# Supply.net
KiCad netlist of a schematic drawn in Altium Designer
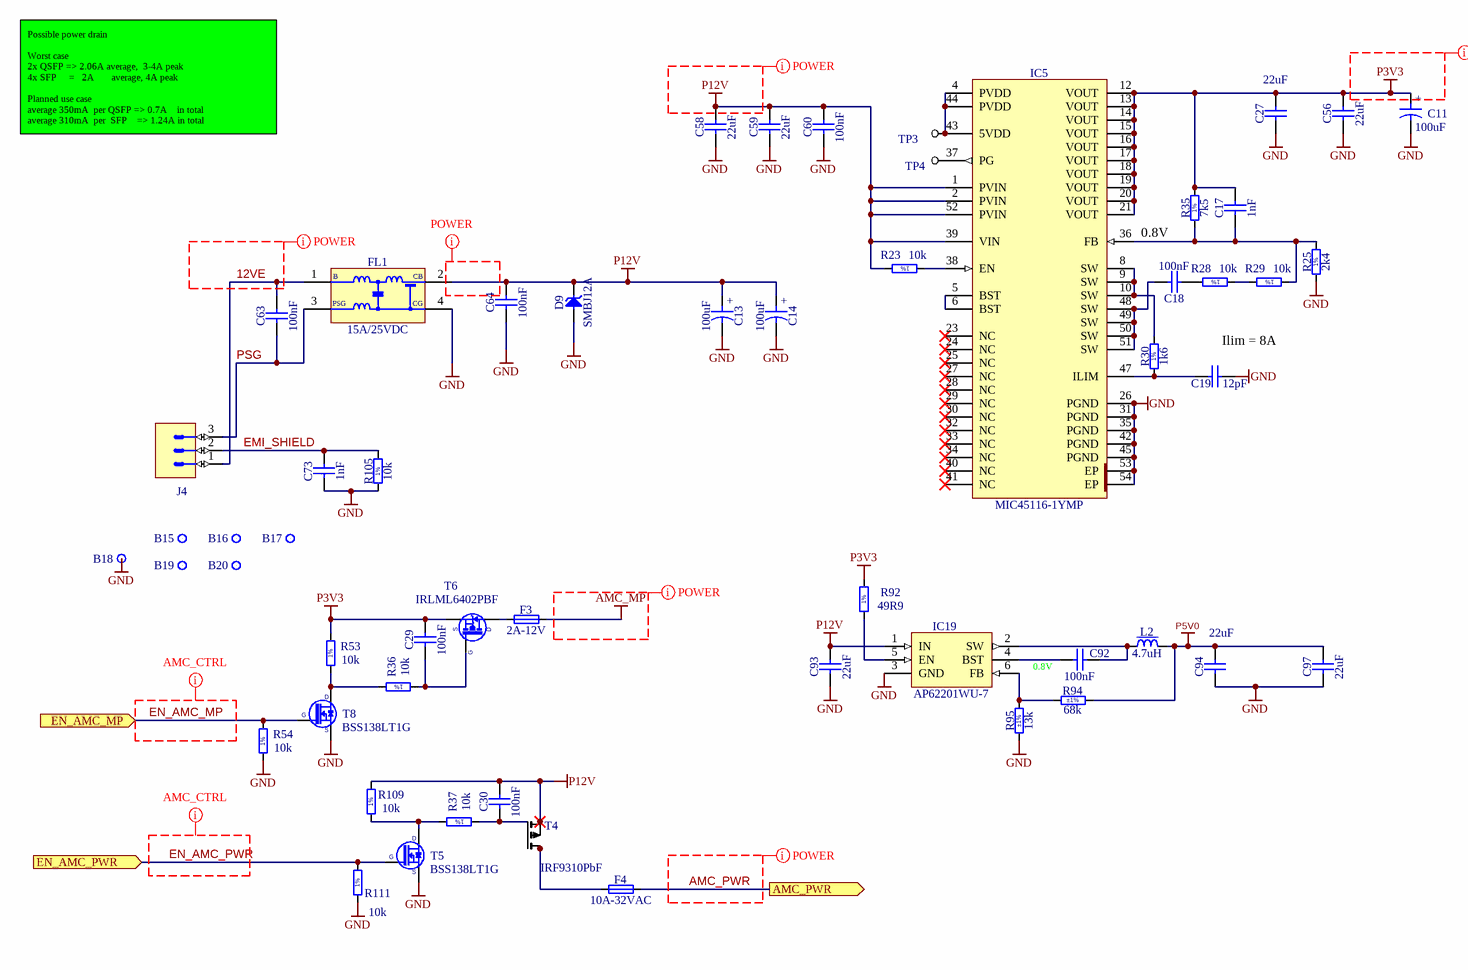
[diagram p0: Supply.SchDoc]

(export (version "E")
  (design (tool "Eeschema 10.0.6"))
  (components
    (comp (ref "B15")
      (value "Plated Hole")
      (footprint "MTG320_550")
      (description "Single Terminal Socket")
      (fields (field (name "PART NUMBER") "PLATED_HOLE3.2_PAD5.5") (field (name "AUTHOR") "CERN DEM JMW"))
      (libsource (lib "Eletro-mechanical") (part "Single Terminal Socket"))
    )
    (comp (ref "B16")
      (value "Plated Hole")
      (footprint "MTG320_550")
      (description "Single Terminal Socket")
      (fields (field (name "PART NUMBER") "PLATED_HOLE3.2_PAD5.5") (field (name "AUTHOR") "CERN DEM JMW"))
      (libsource (lib "Eletro-mechanical") (part "Single Terminal Socket"))
    )
    (comp (ref "B17")
      (value "Plated Hole")
      (footprint "MTG320_550")
      (description "Single Terminal Socket")
      (fields (field (name "PART NUMBER") "PLATED_HOLE3.2_PAD5.5") (field (name "AUTHOR") "CERN DEM JMW"))
      (libsource (lib "Eletro-mechanical") (part "Single Terminal Socket"))
    )
    (comp (ref "B18")
      (value "Plated Hole")
      (footprint "MTG320_550")
      (description "Single Terminal Socket")
      (fields (field (name "PART NUMBER") "PLATED_HOLE3.2_PAD5.5") (field (name "AUTHOR") "CERN DEM JMW"))
      (libsource (lib "Eletro-mechanical") (part "Single Terminal Socket"))
    )
    (comp (ref "B19")
      (value "Plated Hole")
      (footprint "MTG320_550")
      (description "Single Terminal Socket")
      (fields (field (name "PART NUMBER") "PLATED_HOLE3.2_PAD5.5") (field (name "AUTHOR") "CERN DEM JMW"))
      (libsource (lib "Eletro-mechanical") (part "Single Terminal Socket"))
    )
    (comp (ref "B20")
      (value "Plated Hole")
      (footprint "MTG320_550")
      (description "Single Terminal Socket")
      (fields (field (name "PART NUMBER") "PLATED_HOLE3.2_PAD5.5") (field (name "AUTHOR") "CERN DEM JMW"))
      (libsource (lib "Eletro-mechanical") (part "Single Terminal Socket"))
    )
    (comp (ref "C11")
      (value "100uF")
      (footprint "CAPAE660X540N")
      (description "Polarised capacitor")
      (fields
        (field (name "PART NUMBER") "CAE660-540_100UF_16V_20%")
        (field (name "VOLTAGE") "16V")
        (field (name "AUTHOR") "CERN DEM JLC")
      )
      (libsource (lib "Capacitors") (part "Capacitor - polarized"))
    )
    (comp (ref "C13")
      (value "100uF")
      (footprint "CAPAE660X540N")
      (description "Polarised capacitor")
      (fields
        (field (name "PART NUMBER") "CAE660-540_100UF_16V_20%")
        (field (name "VOLTAGE") "16V")
        (field (name "AUTHOR") "CERN DEM JLC")
      )
      (libsource (lib "Capacitors") (part "Capacitor - polarized"))
    )
    (comp (ref "C14")
      (value "100uF")
      (footprint "CAPAE660X540N")
      (description "Polarised capacitor")
      (fields
        (field (name "PART NUMBER") "CAE660-540_100UF_16V_20%")
        (field (name "VOLTAGE") "16V")
        (field (name "AUTHOR") "CERN DEM JLC")
      )
      (libsource (lib "Capacitors") (part "Capacitor - polarized"))
    )
    (comp (ref "C17")
      (value "1nF")
      (footprint "CAPC1005X55N")
      (description "Non-polarised capacitor")
      (fields
        (field (name "PART NUMBER") "CC0402_1NF_50V_10%_X7R")
        (field (name "VOLTAGE") "50V")
        (field (name "AUTHOR") "CERN DEM JLC")
      )
      (libsource (lib "Capacitors") (part "Capacitor - non polarized"))
    )
    (comp (ref "C18")
      (value "100nF")
      (footprint "CAPC1005X55N")
      (description "Non-polarised capacitor")
      (fields
        (field (name "PART NUMBER") "CC0402_100NF_16V_10%_X5R")
        (field (name "VOLTAGE") "16V")
        (field (name "AUTHOR") "CERN DEM JLC")
      )
      (libsource (lib "Capacitors") (part "Capacitor - non polarized"))
    )
    (comp (ref "C19")
      (value "12pF")
      (footprint "CAPC1005X55N")
      (description "Non-polarised capacitor")
      (fields
        (field (name "PART NUMBER") "CC0402_12PF_50V_5%_C0G")
        (field (name "VOLTAGE") "50V")
        (field (name "AUTHOR") "CERN DEM JLC")
      )
      (libsource (lib "Capacitors") (part "Capacitor - non polarized"))
    )
    (comp (ref "C27")
      (value "22uF")
      (footprint "CAPC2012X145N")
      (description "Non-polarised capacitor")
      (fields
        (field (name "PART NUMBER") "CC0805_22UF_25V_20%_X5R")
        (field (name "VOLTAGE") "25V")
        (field (name "AUTHOR") "CERN DEM WB")
      )
      (libsource (lib "Capacitors") (part "Capacitor - non polarized"))
    )
    (comp (ref "C29")
      (value "100nF")
      (footprint "CAPC1005X55N")
      (description "Non-polarised capacitor")
      (fields
        (field (name "PART NUMBER") "CC0402_100NF_16V_10%_X5R")
        (field (name "VOLTAGE") "16V")
        (field (name "AUTHOR") "CERN DEM JLC")
      )
      (libsource (lib "Capacitors") (part "Capacitor - non polarized"))
    )
    (comp (ref "C30")
      (value "100nF")
      (footprint "CAPC1005X55N")
      (description "Non-polarised capacitor")
      (fields
        (field (name "PART NUMBER") "CC0402_100NF_16V_10%_X5R")
        (field (name "VOLTAGE") "16V")
        (field (name "AUTHOR") "CERN DEM JLC")
      )
      (libsource (lib "Capacitors") (part "Capacitor - non polarized"))
    )
    (comp (ref "C56")
      (value "22uF")
      (footprint "CAPC2012X145N")
      (description "Non-polarised capacitor")
      (fields
        (field (name "PART NUMBER") "CC0805_22UF_25V_20%_X5R")
        (field (name "VOLTAGE") "25V")
        (field (name "AUTHOR") "CERN DEM WB")
      )
      (libsource (lib "Capacitors") (part "Capacitor - non polarized"))
    )
    (comp (ref "C58")
      (value "22uF")
      (footprint "CAPC2012X145N")
      (description "Non-polarised capacitor")
      (fields
        (field (name "PART NUMBER") "CC0805_22UF_25V_20%_X5R")
        (field (name "VOLTAGE") "25V")
        (field (name "AUTHOR") "CERN DEM WB")
      )
      (libsource (lib "Capacitors") (part "Capacitor - non polarized"))
    )
    (comp (ref "C59")
      (value "22uF")
      (footprint "CAPC2012X145N")
      (description "Non-polarised capacitor")
      (fields
        (field (name "PART NUMBER") "CC0805_22UF_25V_20%_X5R")
        (field (name "VOLTAGE") "25V")
        (field (name "AUTHOR") "CERN DEM WB")
      )
      (libsource (lib "Capacitors") (part "Capacitor - non polarized"))
    )
    (comp (ref "C60")
      (value "100nF")
      (footprint "CAPC1005X55N")
      (description "Non-polarised capacitor")
      (fields
        (field (name "PART NUMBER") "CC0402_100NF_16V_10%_X5R")
        (field (name "VOLTAGE") "16V")
        (field (name "AUTHOR") "CERN DEM JLC")
      )
      (libsource (lib "Capacitors") (part "Capacitor - non polarized"))
    )
    (comp (ref "C63")
      (value "100nF")
      (footprint "CAPC1005X55N")
      (description "Non-polarised capacitor")
      (fields
        (field (name "PART NUMBER") "CC0402_100NF_16V_10%_X5R")
        (field (name "VOLTAGE") "16V")
        (field (name "AUTHOR") "CERN DEM JLC")
      )
      (libsource (lib "Capacitors") (part "Capacitor - non polarized"))
    )
    (comp (ref "C64")
      (value "100nF")
      (footprint "CAPC1005X55N")
      (description "Non-polarised capacitor")
      (fields
        (field (name "PART NUMBER") "CC0402_100NF_16V_10%_X5R")
        (field (name "VOLTAGE") "16V")
        (field (name "AUTHOR") "CERN DEM JLC")
      )
      (libsource (lib "Capacitors") (part "Capacitor - non polarized"))
    )
    (comp (ref "C73")
      (value "1nF")
      (footprint "CAPC1005X55N")
      (description "Non-polarised capacitor")
      (fields
        (field (name "PART NUMBER") "CC0402_1NF_50V_10%_X7R")
        (field (name "VOLTAGE") "50V")
        (field (name "AUTHOR") "CERN DEM JLC")
      )
      (libsource (lib "Capacitors") (part "Capacitor - non polarized"))
    )
    (comp (ref "C92")
      (value "100nF")
      (footprint "CAPC1005X55N")
      (description "Non-polarised capacitor")
      (fields
        (field (name "PART NUMBER") "CC0402_100NF_16V_10%_X5R")
        (field (name "VOLTAGE") "16V")
        (field (name "AUTHOR") "CERN DEM JLC")
      )
      (libsource (lib "Capacitors") (part "Capacitor - non polarized"))
    )
    (comp (ref "C93")
      (value "22uF")
      (footprint "CAPC2012X145N")
      (description "Non-polarised capacitor")
      (fields
        (field (name "PART NUMBER") "CC0805_22UF_25V_20%_X5R")
        (field (name "VOLTAGE") "25V")
        (field (name "AUTHOR") "CERN DEM WB")
      )
      (libsource (lib "Capacitors") (part "Capacitor - non polarized"))
    )
    (comp (ref "C94")
      (value "22uF")
      (footprint "CAPC2012X145N")
      (description "Non-polarised capacitor")
      (fields
        (field (name "PART NUMBER") "CC0805_22UF_25V_20%_X5R")
        (field (name "VOLTAGE") "25V")
        (field (name "AUTHOR") "CERN DEM WB")
      )
      (libsource (lib "Capacitors") (part "Capacitor - non polarized"))
    )
    (comp (ref "C97")
      (value "22uF")
      (footprint "CAPC2012X145N")
      (description "Non-polarised capacitor")
      (fields
        (field (name "PART NUMBER") "CC0805_22UF_25V_20%_X5R")
        (field (name "VOLTAGE") "25V")
        (field (name "AUTHOR") "CERN DEM WB")
      )
      (libsource (lib "Capacitors") (part "Capacitor - non polarized"))
    )
    (comp (ref "D9")
      (value "SMBJ12A")
      (footprint "DIOM5336X265N")
      (description "Zener Diode")
      (fields
        (field (name "VOLTAGE") "12V")
        (field (name "POWER") "600W")
        (field (name "AUTHOR") "CERN DEM JLC")
      )
      (libsource (lib "ICs And Semiconductors") (part "Diode Zener"))
    )
    (comp (ref "F3")
      (value "2A-12V")
      (footprint "FUSR_LITTELFUSE_1812L200")
      (description "Fuse")
      (fields
        (field (name "PART NUMBER") "FUSR1812_LITTELFUSE_1812L200/12")
        (field (name "MANUFACTURER") "LITTELFUSE")
        (field (name "AUTHOR") "CERN DEM BC")
      )
      (libsource (lib "Eletro-mechanical") (part "Fuse"))
    )
    (comp (ref "F4")
      (value "10A-32VAC")
      (footprint "FUSE_SCHURTER_UST1206")
      (description "Fuse")
      (fields
        (field (name "PART NUMBER") "FUSE_SCHURTER_3413.0328.22")
        (field (name "MANUFACTURER") "SCHURTER")
        (field (name "AUTHOR") "CERN DEM BC")
      )
      (libsource (lib "Eletro-mechanical") (part "Fuse"))
    )
    (comp (ref "FL1")
      (value "15A/25VDC")
      (footprint "FIL_MURATA_BNX016")
      (description "Block Type EMIFIL (LC Combined) SMD Type, BNX01* Serie")
      (fields
        (field (name "PART NUMBER") "FIL_MURATA_BNX016-01")
        (field (name "MANUFACTURER") "MURATA")
        (field (name "AUTHOR") "CERN DEM JLC")
      )
      (libsource (lib "Inductors & Transformers") (part "FIL_MURATA_BNX016"))
    )
    (comp (ref "IC5")
      (value "MIC45116-1YMP")
      (footprint "MICROCHIP_H3QFN88-52LD-PL-3")
      (description "0.8V to 85% PVIN (4.75-19V), 6A Synchronous Step-Down Regulator Module")
      (fields (field (name "MANUFACTURER") "MICROCHIP TECHNOLOGY") (field (name "AUTHOR") "CERN DEM JMW"))
      (libsource (lib "ICs And Semiconductors") (part "MIC45116"))
    )
    (comp (ref "IC19")
      (value "AP62201WU-7")
      (footprint "SOT95P285X110-6N")
      (description "LIGHT LOAD IMPROVED 1.5A SYNCH DC/DC BUCK CONVERTER")
      (fields (field (name "MANUFACTURER") "DIODES INCORPORATED") (field (name "AUTHOR") "GK"))
      (libsource (lib "Regulators_SMPS") (part "PM_AP65111A"))
    )
    (comp (ref "J4")
      (value "~")
      (footprint "PHOENIX_1755749")
      (description "Connector 3 Male")
      (fields
        (field (name "PART NUMBER") "PHOENIX_1755749")
        (field (name "MANUFACTURER") "PHOENIX CONTACT")
        (field (name "AUTHOR") "CERN DEM JLC")
      )
      (libsource (lib "Connectors") (part "Connector 3 Male"))
    )
    (comp (ref "L2")
      (value "4.7uH")
      (footprint "INDM5552X200N")
      (description "Inductor With Core")
      (fields
        (field (name "PART NUMBER") "IND2020_4.7UH_20%_VISHAY_IHLP-2020BZ-11")
        (field (name "POWER") "3.2A")
        (field (name "AUTHOR") "CERN DEM JLC")
      )
      (libsource (lib "Inductors & Transformers") (part "Inductor With Magnetic core"))
    )
    (comp (ref "R23")
      (value "10k")
      (footprint "RESC1005X40N")
      (description "Resistor - 1%")
      (fields
        (field (name "PART NUMBER") "R0402_10K_1%_0.0625W_100PPM")
        (field (name "POWER") "0.0625W")
        (field (name "AUTHOR") "CERN DEM JLC")
      )
      (libsource (lib "Resistors") (part "Resistor - 1%"))
    )
    (comp (ref "R25")
      (value "2k4")
      (footprint "RESC1005X40N")
      (description "Resistor - 1%")
      (fields
        (field (name "PART NUMBER") "R0402_2K4_1%_0.0625W_100PPM")
        (field (name "POWER") "0.0625W")
        (field (name "AUTHOR") "CERN DEM JLC")
      )
      (libsource (lib "Resistors") (part "Resistor - 1%"))
    )
    (comp (ref "R28")
      (value "10k")
      (footprint "RESC1005X40N")
      (description "Resistor - 1%")
      (fields
        (field (name "PART NUMBER") "R0402_10K_1%_0.0625W_100PPM")
        (field (name "POWER") "0.0625W")
        (field (name "AUTHOR") "CERN DEM JLC")
      )
      (libsource (lib "Resistors") (part "Resistor - 1%"))
    )
    (comp (ref "R29")
      (value "10k")
      (footprint "RESC1005X40N")
      (description "Resistor - 1%")
      (fields
        (field (name "PART NUMBER") "R0402_10K_1%_0.0625W_100PPM")
        (field (name "POWER") "0.0625W")
        (field (name "AUTHOR") "CERN DEM JLC")
      )
      (libsource (lib "Resistors") (part "Resistor - 1%"))
    )
    (comp (ref "R30")
      (value "1k6")
      (footprint "RESC1005X40N")
      (description "Resistor - 1%")
      (fields
        (field (name "PART NUMBER") "R0402_1K6_1%_0.0625W_100PPM")
        (field (name "POWER") "0.0625W")
        (field (name "AUTHOR") "CERN DEM JLC")
      )
      (libsource (lib "Resistors") (part "Resistor - 1%"))
    )
    (comp (ref "R35")
      (value "7k5")
      (footprint "RESC1005X40N")
      (description "Resistor - 1%")
      (fields
        (field (name "PART NUMBER") "R0402_7K5_1%_0.0625W_100PPM")
        (field (name "POWER") "0.0625W")
        (field (name "AUTHOR") "CERN DEM JLC")
      )
      (libsource (lib "Resistors") (part "Resistor - 1%"))
    )
    (comp (ref "R36")
      (value "10k")
      (footprint "RESC1005X40N")
      (description "Resistor - 1%")
      (fields
        (field (name "PART NUMBER") "R0402_10K_1%_0.0625W_100PPM")
        (field (name "POWER") "0.0625W")
        (field (name "AUTHOR") "CERN DEM JLC")
      )
      (libsource (lib "Resistors") (part "Resistor - 1%"))
    )
    (comp (ref "R37")
      (value "10k")
      (footprint "RESC1005X40N")
      (description "Resistor - 1%")
      (fields
        (field (name "PART NUMBER") "R0402_10K_1%_0.0625W_100PPM")
        (field (name "POWER") "0.0625W")
        (field (name "AUTHOR") "CERN DEM JLC")
      )
      (libsource (lib "Resistors") (part "Resistor - 1%"))
    )
    (comp (ref "R53")
      (value "10k")
      (footprint "RESC1005X40N")
      (description "Resistor - 1%")
      (fields
        (field (name "PART NUMBER") "R0402_10K_1%_0.0625W_100PPM")
        (field (name "POWER") "0.0625W")
        (field (name "AUTHOR") "CERN DEM JLC")
      )
      (libsource (lib "Resistors") (part "Resistor - 1%"))
    )
    (comp (ref "R54")
      (value "10k")
      (footprint "RESC1005X40N")
      (description "Resistor - 1%")
      (fields
        (field (name "PART NUMBER") "R0402_10K_1%_0.0625W_100PPM")
        (field (name "POWER") "0.0625W")
        (field (name "AUTHOR") "CERN DEM JLC")
      )
      (libsource (lib "Resistors") (part "Resistor - 1%"))
    )
    (comp (ref "R92")
      (value "49R9")
      (footprint "RESC1005X40N")
      (description "Resistor - 1%")
      (fields
        (field (name "PART NUMBER") "R0402_49R9_1%_0.0625W_100PPM")
        (field (name "POWER") "0.0625W")
        (field (name "AUTHOR") "CERN DEM JLC")
      )
      (libsource (lib "Resistors") (part "Resistor - 1%"))
    )
    (comp (ref "R94")
      (value "68k")
      (footprint "RESC1005X40N")
      (description "Resistor - 1%")
      (fields
        (field (name "TOLERANCE") "±1%")
        (field (name "PART NUMBER") "R0402_68K_1%_0.0625W_100PPM")
        (field (name "POWER") "0.0625W")
        (field (name "AUTHOR") "CERN DEM JLC")
      )
      (libsource (lib "Resistors") (part "Resistor - 1%"))
    )
    (comp (ref "R95")
      (value "13k")
      (footprint "RESC1005X40N")
      (description "Resistor - 1%")
      (fields
        (field (name "TOLERANCE") "±1%")
        (field (name "PART NUMBER") "R0402_13K_1%_0.0625W_100PPM")
        (field (name "POWER") "0.0625W")
        (field (name "AUTHOR") "CERN DEM JLC")
      )
      (libsource (lib "Resistors") (part "Resistor - 1%"))
    )
    (comp (ref "R105")
      (value "10k")
      (footprint "RESC1005X40N")
      (description "Resistor - 1%")
      (fields
        (field (name "PART NUMBER") "R0402_10K_1%_0.0625W_100PPM")
        (field (name "POWER") "0.0625W")
        (field (name "AUTHOR") "CERN DEM JLC")
      )
      (libsource (lib "Resistors") (part "Resistor - 1%"))
    )
    (comp (ref "R109")
      (value "10k")
      (footprint "RESC1005X40N")
      (description "Resistor - 1%")
      (fields
        (field (name "PART NUMBER") "R0402_10K_1%_0.0625W_100PPM")
        (field (name "POWER") "0.0625W")
        (field (name "AUTHOR") "CERN DEM JLC")
      )
      (libsource (lib "Resistors") (part "Resistor - 1%"))
    )
    (comp (ref "R111")
      (value "10k")
      (footprint "RESC1005X40N")
      (description "Resistor - 1%")
      (fields
        (field (name "PART NUMBER") "R0402_10K_1%_0.0625W_100PPM")
        (field (name "POWER") "0.0625W")
        (field (name "AUTHOR") "CERN DEM JLC")
      )
      (libsource (lib "Resistors") (part "Resistor - 1%"))
    )
    (comp (ref "T4")
      (value "IRF9310PbF")
      (footprint "so-8")
      (description "PMOS 30V, 4.6mR, 20A, 2.5W")
      (libsource (lib "LIBRARY_SCH") (part "Q_IRF9310"))
    )
    (comp (ref "T5")
      (value "BSS138LT1G")
      (footprint "SOT95P240X110-3N")
      (description "N-CHANNEL MOSFET WITH DIODE")
      (fields (field (name "MANUFACTURER") "ON SEMICONDUCTOR") (field (name "AUTHOR") "CERN DEM JLC"))
      (libsource (lib "ICs And Semiconductors") (part "N-MOSFET-D 1G 2S 3D"))
    )
    (comp (ref "T6")
      (value "IRLML6402PBF")
      (footprint "SOT95P237X112-3N")
      (description "P-CHANNEL MOSFET WITH ZENER DIODE")
      (fields (field (name "MANUFACTURER") "INTERNATIONAL RECTIFIER") (field (name "AUTHOR") "CERN DEM JLC"))
      (libsource (lib "ICs And Semiconductors") (part "P-MOSFET-DZ 1G 2S 3D"))
    )
    (comp (ref "T8")
      (value "BSS138LT1G")
      (footprint "SOT95P240X110-3N")
      (description "N-CHANNEL MOSFET WITH DIODE")
      (fields (field (name "MANUFACTURER") "ON SEMICONDUCTOR") (field (name "AUTHOR") "CERN DEM JLC"))
      (libsource (lib "ICs And Semiconductors") (part "N-MOSFET-D 1G 2S 3D"))
    )
    (comp (ref "TP3")
      (value "TP")
      (footprint "TP")
      (description "Testpoint")
      (libsource (lib "LIBRARY_SCH") (part "TP"))
    )
    (comp (ref "TP4")
      (value "TP")
      (footprint "TP")
      (description "Testpoint")
      (libsource (lib "LIBRARY_SCH") (part "TP"))
    )
  )
  (nets
    (net (code "1") (name "/12VE") (class "Default")
      (node (ref "C63") (pin "2") (pinfunction "2_2") (pintype "passive"))
      (node (ref "FL1") (pin "1") (pinfunction "B_1") (pintype "passive"))
      (node (ref "J4") (pin "1") (pinfunction "1_1") (pintype "bidirectional"))
    )
    (net (code "2") (name "/AMC_PWR") (class "Default")
      (node (ref "F4") (pin "2") (pinfunction "2_2") (pintype "passive"))
    )
    (net (code "3") (name "/EMI_SHIELD") (class "Default")
      (node (ref "C73") (pin "2") (pinfunction "2_2") (pintype "passive"))
      (node (ref "J4") (pin "2") (pinfunction "2_2") (pintype "bidirectional"))
      (node (ref "R105") (pin "2") (pinfunction "2_2") (pintype "passive"))
    )
    (net (code "4") (name "/EN_AMC_MP") (class "Default")
      (node (ref "R54") (pin "2") (pinfunction "2_2") (pintype "passive"))
      (node (ref "T8") (pin "1") (pinfunction "G_1") (pintype "passive"))
    )
    (net (code "5") (name "/EN_AMC_PWR") (class "Default")
      (node (ref "R111") (pin "2") (pinfunction "2_2") (pintype "passive"))
      (node (ref "T5") (pin "1") (pinfunction "G_1") (pintype "passive"))
    )
    (net (code "6") (name "/PSG") (class "Default")
      (node (ref "C63") (pin "1") (pinfunction "1_1") (pintype "passive"))
      (node (ref "FL1") (pin "3") (pinfunction "PSG_3") (pintype "passive"))
      (node (ref "J4") (pin "3") (pinfunction "3_3") (pintype "bidirectional"))
    )
    (net (code "7") (name "AMC_MP") (class "Default")
      (node (ref "F3") (pin "2") (pinfunction "2_2") (pintype "passive"))
    )
    (net (code "8") (name "GND") (class "Default")
      (node (ref "B18") (pin "1") (pinfunction "1_1") (pintype "bidirectional"))
      (node (ref "C11") (pin "2") (pinfunction "2_2") (pintype "passive"))
      (node (ref "C13") (pin "2") (pinfunction "2_2") (pintype "passive"))
      (node (ref "C14") (pin "2") (pinfunction "2_2") (pintype "passive"))
      (node (ref "C19") (pin "1") (pinfunction "1_1") (pintype "passive"))
      (node (ref "C27") (pin "1") (pinfunction "1_1") (pintype "passive"))
      (node (ref "C56") (pin "1") (pinfunction "1_1") (pintype "passive"))
      (node (ref "C58") (pin "1") (pinfunction "1_1") (pintype "passive"))
      (node (ref "C59") (pin "1") (pinfunction "1_1") (pintype "passive"))
      (node (ref "C60") (pin "1") (pinfunction "1_1") (pintype "passive"))
      (node (ref "C64") (pin "1") (pinfunction "1_1") (pintype "passive"))
      (node (ref "C73") (pin "1") (pinfunction "1_1") (pintype "passive"))
      (node (ref "C93") (pin "1") (pinfunction "1_1") (pintype "passive"))
      (node (ref "C94") (pin "1") (pinfunction "1_1") (pintype "passive"))
      (node (ref "C97") (pin "1") (pinfunction "1_1") (pintype "passive"))
      (node (ref "D9") (pin "2") (pinfunction "A_2") (pintype "passive"))
      (node (ref "FL1") (pin "4") (pinfunction "CG_4") (pintype "passive"))
      (node (ref "IC19") (pin "3") (pinfunction "GND_3") (pintype "power_in"))
      (node (ref "IC5") (pin "26") (pinfunction "PGND_26") (pintype "power_in"))
      (node (ref "IC5") (pin "31") (pinfunction "PGND_31") (pintype "power_in"))
      (node (ref "IC5") (pin "35") (pinfunction "PGND_35") (pintype "power_in"))
      (node (ref "IC5") (pin "42") (pinfunction "PGND_42") (pintype "power_in"))
      (node (ref "IC5") (pin "45") (pinfunction "PGND_45") (pintype "power_in"))
      (node (ref "IC5") (pin "53") (pinfunction "EP_53") (pintype "power_in"))
      (node (ref "IC5") (pin "54") (pinfunction "EP_54") (pintype "power_in"))
      (node (ref "R105") (pin "1") (pinfunction "1_1") (pintype "passive"))
      (node (ref "R111") (pin "1") (pinfunction "1_1") (pintype "passive"))
      (node (ref "R25") (pin "1") (pinfunction "1_1") (pintype "passive"))
      (node (ref "R54") (pin "1") (pinfunction "1_1") (pintype "passive"))
      (node (ref "R95") (pin "1") (pinfunction "1_1") (pintype "passive"))
      (node (ref "T5") (pin "2") (pinfunction "S_2") (pintype "passive"))
      (node (ref "T8") (pin "2") (pinfunction "S_2") (pintype "passive"))
    )
    (net (code "9") (name "Net-(C18-Pad1)") (class "Default")
      (node (ref "C18") (pin "1") (pinfunction "1_1") (pintype "passive"))
      (node (ref "R28") (pin "2") (pinfunction "2_2") (pintype "passive"))
    )
    (net (code "10") (name "Net-(C18-Pad2)") (class "Default")
      (node (ref "C18") (pin "2") (pinfunction "2_2") (pintype "passive"))
      (node (ref "IC5") (pin "48") (pinfunction "SW_48") (pintype "passive"))
      (node (ref "IC5") (pin "49") (pinfunction "SW_49") (pintype "passive"))
      (node (ref "IC5") (pin "50") (pinfunction "SW_50") (pintype "passive"))
      (node (ref "IC5") (pin "51") (pinfunction "SW_51") (pintype "passive"))
    )
    (net (code "11") (name "Net-(F4-Pad1)") (class "Default")
      (node (ref "F4") (pin "1") (pinfunction "1_1") (pintype "passive"))
      (node (ref "T4") (pin "5") (pinfunction "D1_5") (pintype "open_collector"))
      (node (ref "T4") (pin "6") (pinfunction "D1_6") (pintype "open_collector"))
      (node (ref "T4") (pin "7") (pinfunction "D1_7") (pintype "open_collector"))
      (node (ref "T4") (pin "8") (pinfunction "D1_8") (pintype "open_collector"))
    )
    (net (code "12") (name "Net-(IC5-5VDD)") (class "Default")
      (node (ref "IC5") (pin "4") (pinfunction "PVDD_4") (pintype "power_in"))
      (node (ref "IC5") (pin "43") (pinfunction "5VDD_43") (pintype "power_in"))
      (node (ref "IC5") (pin "44") (pinfunction "PVDD_44") (pintype "power_in"))
      (node (ref "TP3") (pin "1") (pintype "passive"))
    )
    (net (code "13") (name "Net-(IC5-BST-Pad5)") (class "Default")
      (node (ref "IC5") (pin "5") (pinfunction "BST_5") (pintype "passive"))
      (node (ref "IC5") (pin "6") (pinfunction "BST_6") (pintype "passive"))
    )
    (net (code "14") (name "Net-(IC5-EN)") (class "Default")
      (node (ref "IC5") (pin "38") (pinfunction "EN_38") (pintype "input"))
      (node (ref "R23") (pin "1") (pinfunction "1_1") (pintype "passive"))
    )
    (net (code "15") (name "Net-(IC5-FB)") (class "Default")
      (node (ref "C17") (pin "1") (pinfunction "1_1") (pintype "passive"))
      (node (ref "IC5") (pin "36") (pinfunction "FB_36") (pintype "input"))
      (node (ref "R25") (pin "2") (pinfunction "2_2") (pintype "passive"))
      (node (ref "R29") (pin "1") (pinfunction "1_1") (pintype "passive"))
      (node (ref "R35") (pin "1") (pinfunction "1_1") (pintype "passive"))
    )
    (net (code "16") (name "Net-(IC5-ILIM)") (class "Default")
      (node (ref "C19") (pin "2") (pinfunction "2_2") (pintype "passive"))
      (node (ref "IC5") (pin "47") (pinfunction "ILIM_47") (pintype "passive"))
      (node (ref "R30") (pin "1") (pinfunction "1_1") (pintype "passive"))
    )
    (net (code "17") (name "Net-(IC5-PG)") (class "Default")
      (node (ref "IC5") (pin "37") (pinfunction "PG_37") (pintype "output"))
      (node (ref "TP4") (pin "1") (pintype "passive"))
    )
    (net (code "18") (name "Net-(IC5-SW-Pad10)") (class "Default")
      (node (ref "IC5") (pin "10") (pinfunction "SW_10") (pintype "passive"))
      (node (ref "IC5") (pin "8") (pinfunction "SW_8") (pintype "passive"))
      (node (ref "IC5") (pin "9") (pinfunction "SW_9") (pintype "passive"))
      (node (ref "R30") (pin "2") (pinfunction "2_2") (pintype "passive"))
    )
    (net (code "19") (name "Net-(IC19-BST)") (class "Default")
      (node (ref "C92") (pin "1") (pinfunction "1_1") (pintype "passive"))
      (node (ref "IC19") (pin "4") (pinfunction "BST_4") (pintype "passive"))
    )
    (net (code "20") (name "Net-(IC19-EN)") (class "Default")
      (node (ref "IC19") (pin "5") (pinfunction "EN_5") (pintype "input"))
      (node (ref "R92") (pin "1") (pinfunction "1_1") (pintype "passive"))
    )
    (net (code "21") (name "Net-(IC19-FB)") (class "Default")
      (node (ref "IC19") (pin "6") (pinfunction "FB_6") (pintype "input"))
      (node (ref "R94") (pin "1") (pinfunction "1_1") (pintype "passive"))
      (node (ref "R95") (pin "2") (pinfunction "2_2") (pintype "passive"))
    )
    (net (code "22") (name "Net-(IC19-SW)") (class "Default")
      (node (ref "C92") (pin "2") (pinfunction "2_2") (pintype "passive"))
      (node (ref "IC19") (pin "2") (pinfunction "SW_2") (pintype "output"))
      (node (ref "L2") (pin "1") (pinfunction "1_1") (pintype "passive"))
    )
    (net (code "23") (name "Net-(R28-Pad1)") (class "Default")
      (node (ref "R28") (pin "1") (pinfunction "1_1") (pintype "passive"))
      (node (ref "R29") (pin "2") (pinfunction "2_2") (pintype "passive"))
    )
    (net (code "24") (name "Net-(T4-G1)") (class "Default")
      (node (ref "C30") (pin "1") (pinfunction "1_1") (pintype "passive"))
      (node (ref "R37") (pin "1") (pinfunction "1_1") (pintype "passive"))
      (node (ref "T4") (pin "4") (pinfunction "G1_4") (pintype "input"))
    )
    (net (code "25") (name "Net-(T5-D)") (class "Default")
      (node (ref "R109") (pin "1") (pinfunction "1_1") (pintype "passive"))
      (node (ref "R37") (pin "2") (pinfunction "2_2") (pintype "passive"))
      (node (ref "T5") (pin "3") (pinfunction "D_3") (pintype "passive"))
    )
    (net (code "26") (name "Net-(T6-D)") (class "Default")
      (node (ref "F3") (pin "1") (pinfunction "1_1") (pintype "passive"))
      (node (ref "T6") (pin "3") (pinfunction "D_3") (pintype "passive"))
    )
    (net (code "27") (name "Net-(T6-G)") (class "Default")
      (node (ref "C29") (pin "1") (pinfunction "1_1") (pintype "passive"))
      (node (ref "R36") (pin "1") (pinfunction "1_1") (pintype "passive"))
      (node (ref "T6") (pin "1") (pinfunction "G_1") (pintype "passive"))
    )
    (net (code "28") (name "Net-(T8-D)") (class "Default")
      (node (ref "R36") (pin "2") (pinfunction "2_2") (pintype "passive"))
      (node (ref "R53") (pin "1") (pinfunction "1_1") (pintype "passive"))
      (node (ref "T8") (pin "3") (pinfunction "D_3") (pintype "passive"))
    )
    (net (code "29") (name "P3V3") (class "Default")
      (node (ref "C11") (pin "1") (pinfunction "1_1") (pintype "passive"))
      (node (ref "C17") (pin "2") (pinfunction "2_2") (pintype "passive"))
      (node (ref "C27") (pin "2") (pinfunction "2_2") (pintype "passive"))
      (node (ref "C29") (pin "2") (pinfunction "2_2") (pintype "passive"))
      (node (ref "C56") (pin "2") (pinfunction "2_2") (pintype "passive"))
      (node (ref "IC5") (pin "12") (pinfunction "VOUT_12") (pintype "power_in"))
      (node (ref "IC5") (pin "13") (pinfunction "VOUT_13") (pintype "power_in"))
      (node (ref "IC5") (pin "14") (pinfunction "VOUT_14") (pintype "power_in"))
      (node (ref "IC5") (pin "15") (pinfunction "VOUT_15") (pintype "power_in"))
      (node (ref "IC5") (pin "16") (pinfunction "VOUT_16") (pintype "power_in"))
      (node (ref "IC5") (pin "17") (pinfunction "VOUT_17") (pintype "power_in"))
      (node (ref "IC5") (pin "18") (pinfunction "VOUT_18") (pintype "power_in"))
      (node (ref "IC5") (pin "19") (pinfunction "VOUT_19") (pintype "power_in"))
      (node (ref "IC5") (pin "20") (pinfunction "VOUT_20") (pintype "power_in"))
      (node (ref "IC5") (pin "21") (pinfunction "VOUT_21") (pintype "power_in"))
      (node (ref "R35") (pin "2") (pinfunction "2_2") (pintype "passive"))
      (node (ref "R53") (pin "2") (pinfunction "2_2") (pintype "passive"))
      (node (ref "R92") (pin "2") (pinfunction "2_2") (pintype "passive"))
      (node (ref "T6") (pin "2") (pinfunction "S_2") (pintype "passive"))
    )
    (net (code "30") (name "P5V0") (class "Default")
      (node (ref "C94") (pin "2") (pinfunction "2_2") (pintype "passive"))
      (node (ref "C97") (pin "2") (pinfunction "2_2") (pintype "passive"))
      (node (ref "L2") (pin "2") (pinfunction "2_2") (pintype "passive"))
      (node (ref "R94") (pin "2") (pinfunction "2_2") (pintype "passive"))
    )
    (net (code "31") (name "P12V") (class "Default")
      (node (ref "C13") (pin "1") (pinfunction "1_1") (pintype "passive"))
      (node (ref "C14") (pin "1") (pinfunction "1_1") (pintype "passive"))
      (node (ref "C30") (pin "2") (pinfunction "2_2") (pintype "passive"))
      (node (ref "C58") (pin "2") (pinfunction "2_2") (pintype "passive"))
      (node (ref "C59") (pin "2") (pinfunction "2_2") (pintype "passive"))
      (node (ref "C60") (pin "2") (pinfunction "2_2") (pintype "passive"))
      (node (ref "C64") (pin "2") (pinfunction "2_2") (pintype "passive"))
      (node (ref "C93") (pin "2") (pinfunction "2_2") (pintype "passive"))
      (node (ref "D9") (pin "1") (pinfunction "C_1") (pintype "passive"))
      (node (ref "FL1") (pin "2") (pinfunction "CB_2") (pintype "passive"))
      (node (ref "IC19") (pin "1") (pinfunction "IN_1") (pintype "input"))
      (node (ref "IC5") (pin "1") (pinfunction "PVIN_1") (pintype "power_in"))
      (node (ref "IC5") (pin "2") (pinfunction "PVIN_2") (pintype "power_in"))
      (node (ref "IC5") (pin "39") (pinfunction "VIN_39") (pintype "power_in"))
      (node (ref "IC5") (pin "52") (pinfunction "PVIN_52") (pintype "power_in"))
      (node (ref "R109") (pin "2") (pinfunction "2_2") (pintype "passive"))
      (node (ref "R23") (pin "2") (pinfunction "2_2") (pintype "passive"))
      (node (ref "T4") (pin "1") (pinfunction "S1_1") (pintype "open_emitter"))
      (node (ref "T4") (pin "2") (pinfunction "S1_2") (pintype "open_emitter"))
      (node (ref "T4") (pin "3") (pinfunction "S1_3") (pintype "open_emitter"))
    )
    (net (code "32") (name "unconnected-(B15-Pad1)") (class "Default")
      (node (ref "B15") (pin "1") (pinfunction "1_1") (pintype "bidirectional"))
    )
    (net (code "33") (name "unconnected-(B16-Pad1)") (class "Default")
      (node (ref "B16") (pin "1") (pinfunction "1_1") (pintype "bidirectional"))
    )
    (net (code "34") (name "unconnected-(B17-Pad1)") (class "Default")
      (node (ref "B17") (pin "1") (pinfunction "1_1") (pintype "bidirectional"))
    )
    (net (code "35") (name "unconnected-(B19-Pad1)") (class "Default")
      (node (ref "B19") (pin "1") (pinfunction "1_1") (pintype "bidirectional"))
    )
    (net (code "36") (name "unconnected-(B20-Pad1)") (class "Default")
      (node (ref "B20") (pin "1") (pinfunction "1_1") (pintype "bidirectional"))
    )
    (net (code "37") (name "unconnected-(IC5-NC-Pad23)") (class "Default")
      (node (ref "IC5") (pin "23") (pinfunction "NC_23") (pintype "passive+no_connect"))
    )
    (net (code "38") (name "unconnected-(IC5-NC-Pad24)") (class "Default")
      (node (ref "IC5") (pin "24") (pinfunction "NC_24") (pintype "passive+no_connect"))
    )
    (net (code "39") (name "unconnected-(IC5-NC-Pad25)") (class "Default")
      (node (ref "IC5") (pin "25") (pinfunction "NC_25") (pintype "passive+no_connect"))
    )
    (net (code "40") (name "unconnected-(IC5-NC-Pad27)") (class "Default")
      (node (ref "IC5") (pin "27") (pinfunction "NC_27") (pintype "passive+no_connect"))
    )
    (net (code "41") (name "unconnected-(IC5-NC-Pad28)") (class "Default")
      (node (ref "IC5") (pin "28") (pinfunction "NC_28") (pintype "passive+no_connect"))
    )
    (net (code "42") (name "unconnected-(IC5-NC-Pad29)") (class "Default")
      (node (ref "IC5") (pin "29") (pinfunction "NC_29") (pintype "passive+no_connect"))
    )
    (net (code "43") (name "unconnected-(IC5-NC-Pad30)") (class "Default")
      (node (ref "IC5") (pin "30") (pinfunction "NC_30") (pintype "passive+no_connect"))
    )
    (net (code "44") (name "unconnected-(IC5-NC-Pad32)") (class "Default")
      (node (ref "IC5") (pin "32") (pinfunction "NC_32") (pintype "passive+no_connect"))
    )
    (net (code "45") (name "unconnected-(IC5-NC-Pad33)") (class "Default")
      (node (ref "IC5") (pin "33") (pinfunction "NC_33") (pintype "passive+no_connect"))
    )
    (net (code "46") (name "unconnected-(IC5-NC-Pad34)") (class "Default")
      (node (ref "IC5") (pin "34") (pinfunction "NC_34") (pintype "passive+no_connect"))
    )
    (net (code "47") (name "unconnected-(IC5-NC-Pad40)") (class "Default")
      (node (ref "IC5") (pin "40") (pinfunction "NC_40") (pintype "passive+no_connect"))
    )
    (net (code "48") (name "unconnected-(IC5-NC-Pad41)") (class "Default")
      (node (ref "IC5") (pin "41") (pinfunction "NC_41") (pintype "passive+no_connect"))
    )
  )
)
